# o_clone_rev_e_buttons.net
KiCad netlist of a schematic drawn in EAGLE
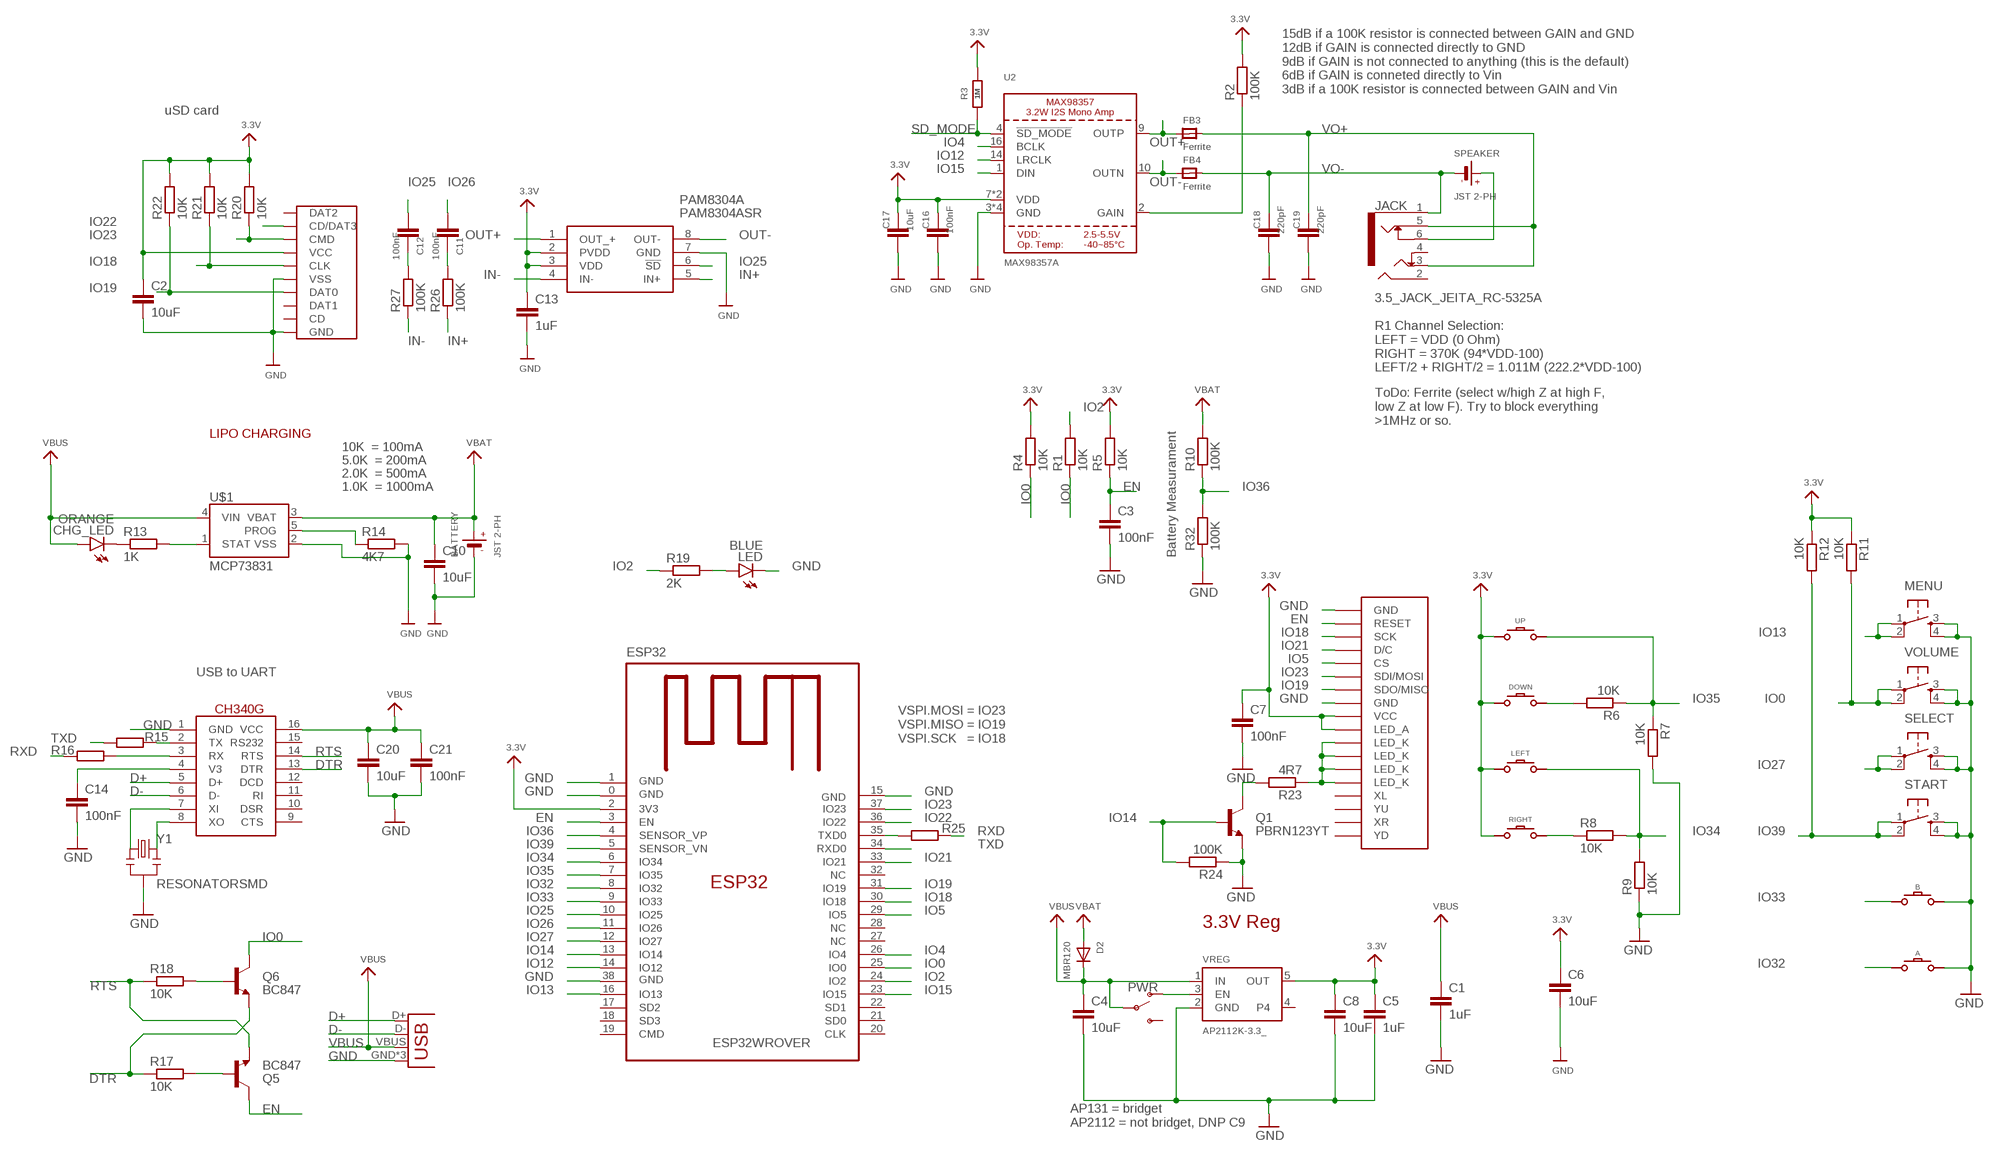
[diagram p0: schematic, sheet 1]

(export (version "E")
  (design (tool "Eeschema 10.0.6"))
  (components
    (comp (ref "A")
      (value "CONDUCTIVE_BUTTONCONDUCTIVE_BUTTON_THICK")
      (footprint "eagle-import:CONDUCTIVE_BUTTON_THICK")
      (libsource (lib "eagle-import") (part "CONDUCTIVE_BUTTONCONDUCTIVE_BUTTON_THICK"))
    )
    (comp (ref "B")
      (value "CONDUCTIVE_BUTTONCONDUCTIVE_BUTTON_THICK")
      (footprint "eagle-import:CONDUCTIVE_BUTTON_THICK")
      (libsource (lib "eagle-import") (part "CONDUCTIVE_BUTTONCONDUCTIVE_BUTTON_THICK"))
    )
    (comp (ref "BATTERY")
      (value "JST 2-PH")
      (footprint "eagle-import:JSTPH2")
      (libsource (lib "eagle-import") (part "JST_CONNECTOR"))
    )
    (comp (ref "C1")
      (value "1uF")
      (footprint "eagle-import:C0805K")
      (libsource (lib "eagle-import") (part "C-EUC0805K"))
    )
    (comp (ref "C2")
      (value "10uF")
      (footprint "eagle-import:C0805K")
      (libsource (lib "eagle-import") (part "C-EUC0805K"))
    )
    (comp (ref "C3")
      (value "100nF")
      (footprint "eagle-import:C0805K")
      (libsource (lib "eagle-import") (part "C-EUC0805K"))
    )
    (comp (ref "C4")
      (value "10uF")
      (footprint "eagle-import:C0805K")
      (libsource (lib "eagle-import") (part "C-EUC0805K"))
    )
    (comp (ref "C5")
      (value "1uF")
      (footprint "eagle-import:C0805K")
      (libsource (lib "eagle-import") (part "C-EUC0805K"))
    )
    (comp (ref "C6")
      (value "10uF")
      (footprint "eagle-import:C0805K")
      (libsource (lib "eagle-import") (part "C-EUC0805K"))
    )
    (comp (ref "C7")
      (value "100nF")
      (footprint "eagle-import:C0805")
      (libsource (lib "eagle-import") (part "C-EUC0805"))
    )
    (comp (ref "C8")
      (value "10uF")
      (footprint "eagle-import:C0805K")
      (libsource (lib "eagle-import") (part "C-EUC0805K"))
    )
    (comp (ref "C10")
      (value "10uF")
      (footprint "eagle-import:C0805K")
      (libsource (lib "eagle-import") (part "C-EUC0805K"))
    )
    (comp (ref "C11")
      (value "100nF")
      (footprint "eagle-import:C0805K")
      (libsource (lib "eagle-import") (part "C-EUC0805K"))
    )
    (comp (ref "C12")
      (value "100nF")
      (footprint "eagle-import:C0805K")
      (libsource (lib "eagle-import") (part "C-EUC0805K"))
    )
    (comp (ref "C13")
      (value "1uF")
      (footprint "eagle-import:C0805K")
      (libsource (lib "eagle-import") (part "C-EUC0805K"))
    )
    (comp (ref "C14")
      (value "100nF")
      (footprint "eagle-import:C0805K")
      (libsource (lib "eagle-import") (part "C-EUC0805K"))
    )
    (comp (ref "C16")
      (value "100nF")
      (footprint "eagle-import:C0805K")
      (libsource (lib "eagle-import") (part "C-EUC0805K"))
    )
    (comp (ref "C17")
      (value "10uF")
      (footprint "eagle-import:C0805K")
      (libsource (lib "eagle-import") (part "C-EUC0805K"))
    )
    (comp (ref "C18")
      (value "220pF")
      (footprint "eagle-import:C0805K")
      (libsource (lib "eagle-import") (part "C-EUC0805K"))
    )
    (comp (ref "C19")
      (value "220pF")
      (footprint "eagle-import:C0805K")
      (libsource (lib "eagle-import") (part "C-EUC0805K"))
    )
    (comp (ref "C20")
      (value "10uF")
      (footprint "eagle-import:C0805K")
      (libsource (lib "eagle-import") (part "C-EUC0805K"))
    )
    (comp (ref "C21")
      (value "100nF")
      (footprint "eagle-import:C0805K")
      (libsource (lib "eagle-import") (part "C-EUC0805K"))
    )
    (comp (ref "CHG_LED")
      (value "ORANGE")
      (footprint "eagle-import:CHIPLED_0805")
      (libsource (lib "eagle-import") (part "LEDCHIPLED_0805"))
    )
    (comp (ref "D2")
      (value "MBR120")
      (footprint "eagle-import:SOD-123")
      (libsource (lib "eagle-import") (part "DIODESOD-123"))
    )
    (comp (ref "DOWN")
      (value "CONDUCTIVE_BUTTONCONDUCTIVE_BUTTON_DIRECTIONAL_THICK")
      (footprint "eagle-import:CONDUCTIVE_BUTTON_DIRECTIONAL_THICK")
      (libsource (lib "eagle-import") (part "CONDUCTIVE_BUTTONCONDUCTIVE_BUTTON_DIRECTIONAL_THICK"))
    )
    (comp (ref "ESP32")
      (value "ESP32WROVER")
      (footprint "eagle-import:ESP32WROVER")
      (libsource (lib "eagle-import") (part "ESP32WROVER"))
    )
    (comp (ref "FB3")
      (value "Ferrite")
      (footprint "eagle-import:0805")
      (libsource (lib "eagle-import") (part "FERRITE0805"))
    )
    (comp (ref "FB4")
      (value "Ferrite")
      (footprint "eagle-import:0805")
      (libsource (lib "eagle-import") (part "FERRITE0805"))
    )
    (comp (ref "JACK")
      (value "3.5_JACK_JEITA_RC-5325A")
      (footprint "eagle-import:3.5_JACK_JEITA_RC-5325A")
      (libsource (lib "eagle-import") (part "3.5_JACK_JEITA_RC-5325A"))
    )
    (comp (ref "LCD")
      (value "ILI9341_3.2LCD_")
      (footprint "eagle-import:LI9341_3.2LCD")
      (libsource (lib "eagle-import") (part "ILI9341_3.2LCD_"))
    )
    (comp (ref "LED")
      (value "BLUE")
      (footprint "eagle-import:CHIPLED_0805")
      (libsource (lib "eagle-import") (part "LEDCHIPLED_0805"))
    )
    (comp (ref "LEFT")
      (value "CONDUCTIVE_BUTTONCONDUCTIVE_BUTTON_DIRECTIONAL_THICK")
      (footprint "eagle-import:CONDUCTIVE_BUTTON_DIRECTIONAL_THICK")
      (libsource (lib "eagle-import") (part "CONDUCTIVE_BUTTONCONDUCTIVE_BUTTON_DIRECTIONAL_THICK"))
    )
    (comp (ref "MENU")
      (value "TACTILE_SWITCHE_5X5_MICRO\"")
      (footprint "eagle-import:TACTILE_SWITCH_5X5_MICRO")
      (libsource (lib "eagle-import") (part "TACTILE_SWITCHE_5X5_MICRO{dblquote}"))
    )
    (comp (ref "PAM8304A")
      (value "PAM8304ASR")
      (footprint "eagle-import:SOP65P490X110-8N")
      (fields (field (name "MOUSER_PART_NUMBER") "621-PAM8304ASR"))
      (libsource (lib "eagle-import") (part "PAM8304ASR"))
    )
    (comp (ref "PWR")
      (value "SWITCH-SPDT-SMD-RIGHT-ANGLE")
      (footprint "eagle-import:SWITCH_SPST_SMD_A")
      (libsource (lib "eagle-import") (part "SWITCH-SPDT-SMD-RIGHT-ANGLE"))
    )
    (comp (ref "Q1")
      (value "PBRN123YT")
      (footprint "eagle-import:SOT23-3")
      (libsource (lib "eagle-import") (part "TRANSISTOR_NPNSOT23-3"))
    )
    (comp (ref "Q5")
      (value "BC847")
      (footprint "eagle-import:SOT23-3")
      (libsource (lib "eagle-import") (part "TRANSISTOR_NPNSOT23-3"))
    )
    (comp (ref "Q6")
      (value "BC847")
      (footprint "eagle-import:SOT23-3")
      (libsource (lib "eagle-import") (part "TRANSISTOR_NPNSOT23-3"))
    )
    (comp (ref "R1")
      (value "10K")
      (footprint "eagle-import:R0805")
      (libsource (lib "eagle-import") (part "R-EU_R0805"))
    )
    (comp (ref "R2")
      (value "100K")
      (footprint "eagle-import:R0805")
      (libsource (lib "eagle-import") (part "R-EU_R0805"))
    )
    (comp (ref "R3")
      (value "1M")
      (footprint "eagle-import:R0805")
      (libsource (lib "eagle-import") (part "R-EU_R0805"))
    )
    (comp (ref "R4")
      (value "10K")
      (footprint "eagle-import:R0805")
      (libsource (lib "eagle-import") (part "R-EU_R0805"))
    )
    (comp (ref "R5")
      (value "10K")
      (footprint "eagle-import:R0805")
      (libsource (lib "eagle-import") (part "R-EU_R0805"))
    )
    (comp (ref "R6")
      (value "10K")
      (footprint "eagle-import:R0805")
      (libsource (lib "eagle-import") (part "R-EU_R0805"))
    )
    (comp (ref "R7")
      (value "10K")
      (footprint "eagle-import:R0805")
      (libsource (lib "eagle-import") (part "R-EU_R0805"))
    )
    (comp (ref "R8")
      (value "10K")
      (footprint "eagle-import:R0805")
      (libsource (lib "eagle-import") (part "R-EU_R0805"))
    )
    (comp (ref "R9")
      (value "10K")
      (footprint "eagle-import:R0805")
      (libsource (lib "eagle-import") (part "R-EU_R0805"))
    )
    (comp (ref "R10")
      (value "100K")
      (footprint "eagle-import:R0805")
      (libsource (lib "eagle-import") (part "R-EU_R0805"))
    )
    (comp (ref "R11")
      (value "10K")
      (footprint "eagle-import:R0805")
      (libsource (lib "eagle-import") (part "R-EU_R0805"))
    )
    (comp (ref "R12")
      (value "10K")
      (footprint "eagle-import:R0805")
      (libsource (lib "eagle-import") (part "R-EU_R0805"))
    )
    (comp (ref "R13")
      (value "1K")
      (footprint "eagle-import:R0805")
      (libsource (lib "eagle-import") (part "R-EU_R0805"))
    )
    (comp (ref "R14")
      (value "4K7")
      (footprint "eagle-import:R0805")
      (libsource (lib "eagle-import") (part "R-EU_R0805"))
    )
    (comp (ref "R15")
      (value "470R")
      (footprint "eagle-import:R0805")
      (libsource (lib "eagle-import") (part "R-EU_R0805"))
    )
    (comp (ref "R16")
      (value "470R")
      (footprint "eagle-import:R0805")
      (libsource (lib "eagle-import") (part "R-EU_R0805"))
    )
    (comp (ref "R17")
      (value "10K")
      (footprint "eagle-import:R0805")
      (libsource (lib "eagle-import") (part "R-EU_R0805"))
    )
    (comp (ref "R18")
      (value "10K")
      (footprint "eagle-import:R0805")
      (libsource (lib "eagle-import") (part "R-EU_R0805"))
    )
    (comp (ref "R19")
      (value "2K")
      (footprint "eagle-import:R0805")
      (libsource (lib "eagle-import") (part "R-EU_R0805"))
    )
    (comp (ref "R20")
      (value "10K")
      (footprint "eagle-import:R0805")
      (libsource (lib "eagle-import") (part "R-EU_R0805"))
    )
    (comp (ref "R21")
      (value "10K")
      (footprint "eagle-import:R0805")
      (libsource (lib "eagle-import") (part "R-EU_R0805"))
    )
    (comp (ref "R22")
      (value "10K")
      (footprint "eagle-import:R0805")
      (libsource (lib "eagle-import") (part "R-EU_R0805"))
    )
    (comp (ref "R23")
      (value "4R7")
      (footprint "eagle-import:R0805")
      (libsource (lib "eagle-import") (part "R-EU_R0805"))
    )
    (comp (ref "R24")
      (value "100K")
      (footprint "eagle-import:R0805")
      (libsource (lib "eagle-import") (part "R-EU_R0805"))
    )
    (comp (ref "R25")
      (value "470R")
      (footprint "eagle-import:R0805")
      (libsource (lib "eagle-import") (part "R-EU_R0805"))
    )
    (comp (ref "R26")
      (value "100K")
      (footprint "eagle-import:R0805")
      (libsource (lib "eagle-import") (part "R-EU_R0805"))
    )
    (comp (ref "R27")
      (value "100K")
      (footprint "eagle-import:R0805")
      (libsource (lib "eagle-import") (part "R-EU_R0805"))
    )
    (comp (ref "R32")
      (value "100K")
      (footprint "eagle-import:R0805")
      (libsource (lib "eagle-import") (part "R-EU_R0805"))
    )
    (comp (ref "RIGHT")
      (value "CONDUCTIVE_BUTTONCONDUCTIVE_BUTTON_DIRECTIONAL_THICK")
      (footprint "eagle-import:CONDUCTIVE_BUTTON_DIRECTIONAL_THICK")
      (libsource (lib "eagle-import") (part "CONDUCTIVE_BUTTONCONDUCTIVE_BUTTON_DIRECTIONAL_THICK"))
    )
    (comp (ref "SD_CARD")
      (value "MICRO_SD_CARD\"")
      (footprint "eagle-import:TFP09-2--12B")
      (libsource (lib "eagle-import") (part "MICRO_SD_CARD{dblquote}"))
    )
    (comp (ref "SELECT")
      (value "TACTILE_SWITCHE_5X5_MICRO\"")
      (footprint "eagle-import:TACTILE_SWITCH_5X5_MICRO")
      (libsource (lib "eagle-import") (part "TACTILE_SWITCHE_5X5_MICRO{dblquote}"))
    )
    (comp (ref "SPEAKER")
      (value "JST 2-PH")
      (footprint "eagle-import:JSTPH2")
      (libsource (lib "eagle-import") (part "JST_CONNECTOR"))
    )
    (comp (ref "START")
      (value "TACTILE_SWITCHE_5X5_MICRO\"")
      (footprint "eagle-import:TACTILE_SWITCH_5X5_MICRO")
      (libsource (lib "eagle-import") (part "TACTILE_SWITCHE_5X5_MICRO{dblquote}"))
    )
    (comp (ref "U$1")
      (value "MCP73831")
      (footprint "eagle-import:SOT95P290X120-5")
      (libsource (lib "eagle-import") (part "MCP73831"))
    )
    (comp (ref "U$23")
      (value "CH340G")
      (footprint "eagle-import:SO16")
      (libsource (lib "eagle-import") (part "CH340G"))
    )
    (comp (ref "U2")
      (value "MAX98357A")
      (footprint "eagle-import:QFN16_3MM")
      (libsource (lib "eagle-import") (part "AUDIOAMP_MAX98357"))
    )
    (comp (ref "UP")
      (value "CONDUCTIVE_BUTTONCONDUCTIVE_BUTTON_DIRECTIONAL_THICK")
      (footprint "eagle-import:CONDUCTIVE_BUTTON_DIRECTIONAL_THICK")
      (libsource (lib "eagle-import") (part "CONDUCTIVE_BUTTONCONDUCTIVE_BUTTON_DIRECTIONAL_THICK"))
    )
    (comp (ref "USB")
      (value "USB_MICRO_ATTEND_")
      (footprint "eagle-import:USB_MICRO")
      (libsource (lib "eagle-import") (part "USB_MICRO_ATTEND_"))
    )
    (comp (ref "VOLUME")
      (value "TACTILE_SWITCHE_5X5_MICRO\"")
      (footprint "eagle-import:TACTILE_SWITCH_5X5_MICRO")
      (libsource (lib "eagle-import") (part "TACTILE_SWITCHE_5X5_MICRO{dblquote}"))
    )
    (comp (ref "VREG")
      (value "AP2112K-3.3_")
      (footprint "eagle-import:SOT95P290X120-5")
      (libsource (lib "eagle-import") (part "AP2112K-3.3_"))
    )
    (comp (ref "Y1")
      (value "RESONATORSMD")
      (footprint "eagle-import:RESONATOR-SMD")
      (libsource (lib "eagle-import") (part "RESONATORSMD"))
    )
  )
  (nets
    (net (code "1") (name "/D+") (class "Default")
      (node (ref "U$23") (pin "5") (pinfunction "D+_5") (pintype "bidirectional"))
      (node (ref "USB") (pin "D+") (pinfunction "D+_D+") (pintype "bidirectional"))
    )
    (net (code "2") (name "/D-") (class "Default")
      (node (ref "U$23") (pin "6") (pinfunction "D-_6") (pintype "bidirectional"))
      (node (ref "USB") (pin "D-") (pinfunction "D-_D-") (pintype "bidirectional"))
    )
    (net (code "3") (name "/DTR") (class "Default")
      (node (ref "Q6") (pin "2") (pinfunction "E_2") (pintype "passive"))
      (node (ref "R17") (pin "1") (pinfunction "1_1") (pintype "passive"))
      (node (ref "U$23") (pin "13") (pinfunction "DTR_13") (pintype "bidirectional"))
    )
    (net (code "4") (name "/EN") (class "Default")
      (node (ref "C3") (pin "1") (pinfunction "1_1") (pintype "passive"))
      (node (ref "ESP32") (pin "3") (pinfunction "EN_3") (pintype "bidirectional"))
      (node (ref "LCD") (pin "P$2") (pinfunction "RESET_P$2") (pintype "bidirectional"))
      (node (ref "Q5") (pin "3") (pinfunction "C_3") (pintype "passive"))
      (node (ref "R5") (pin "1") (pinfunction "1_1") (pintype "passive"))
    )
    (net (code "5") (name "/IN+") (class "Default")
      (node (ref "PAM8304A") (pin "5") (pinfunction "IN+_5") (pintype "bidirectional"))
      (node (ref "R26") (pin "1") (pinfunction "1_1") (pintype "passive"))
    )
    (net (code "6") (name "/IN-") (class "Default")
      (node (ref "PAM8304A") (pin "4") (pinfunction "IN-_4") (pintype "bidirectional"))
      (node (ref "R27") (pin "1") (pinfunction "1_1") (pintype "passive"))
    )
    (net (code "7") (name "/IO0") (class "Default")
      (node (ref "ESP32") (pin "25") (pinfunction "IO0_25") (pintype "bidirectional"))
      (node (ref "Q6") (pin "3") (pinfunction "C_3") (pintype "passive"))
      (node (ref "R1") (pin "1") (pinfunction "1_1") (pintype "passive"))
      (node (ref "R11") (pin "2") (pinfunction "2_2") (pintype "passive"))
      (node (ref "R4") (pin "1") (pinfunction "1_1") (pintype "passive"))
      (node (ref "VOLUME") (pin "1") (pinfunction "1_1") (pintype "passive"))
      (node (ref "VOLUME") (pin "2") (pinfunction "2_2") (pintype "passive"))
    )
    (net (code "8") (name "/IO2") (class "Default")
      (node (ref "ESP32") (pin "24") (pinfunction "IO2_24") (pintype "bidirectional"))
      (node (ref "R1") (pin "2") (pinfunction "2_2") (pintype "passive"))
      (node (ref "R19") (pin "1") (pinfunction "1_1") (pintype "passive"))
    )
    (net (code "9") (name "/IO4") (class "Default")
      (node (ref "ESP32") (pin "26") (pinfunction "IO4_26") (pintype "bidirectional"))
      (node (ref "U2") (pin "16") (pinfunction "BCLK_16") (pintype "bidirectional"))
    )
    (net (code "10") (name "/IO5") (class "Default")
      (node (ref "ESP32") (pin "29") (pinfunction "IO5_29") (pintype "bidirectional"))
      (node (ref "LCD") (pin "P$5") (pinfunction "CS_P$5") (pintype "bidirectional"))
    )
    (net (code "11") (name "/IO12") (class "Default")
      (node (ref "ESP32") (pin "14") (pinfunction "IO12_14") (pintype "bidirectional"))
      (node (ref "U2") (pin "14") (pinfunction "LRCLK_14") (pintype "bidirectional"))
    )
    (net (code "12") (name "/IO13") (class "Default")
      (node (ref "ESP32") (pin "16") (pinfunction "IO13_16") (pintype "bidirectional"))
      (node (ref "MENU") (pin "1") (pinfunction "1_1") (pintype "passive"))
      (node (ref "MENU") (pin "2") (pinfunction "2_2") (pintype "passive"))
    )
    (net (code "13") (name "/IO14") (class "Default")
      (node (ref "ESP32") (pin "13") (pinfunction "IO14_13") (pintype "bidirectional"))
      (node (ref "Q1") (pin "1") (pinfunction "B_1") (pintype "passive"))
      (node (ref "R24") (pin "2") (pinfunction "2_2") (pintype "passive"))
    )
    (net (code "14") (name "/IO15") (class "Default")
      (node (ref "ESP32") (pin "23") (pinfunction "IO15_23") (pintype "bidirectional"))
      (node (ref "U2") (pin "1") (pinfunction "DIN_1") (pintype "bidirectional"))
    )
    (net (code "15") (name "/IO18") (class "Default")
      (node (ref "ESP32") (pin "30") (pinfunction "IO18_30") (pintype "bidirectional"))
      (node (ref "LCD") (pin "P$3") (pinfunction "SCK_P$3") (pintype "bidirectional"))
      (node (ref "R21") (pin "1") (pinfunction "1_1") (pintype "passive"))
      (node (ref "SD_CARD") (pin "CLK") (pinfunction "CLK_CLK") (pintype "bidirectional"))
    )
    (net (code "16") (name "/IO19") (class "Default")
      (node (ref "ESP32") (pin "31") (pinfunction "IO19_31") (pintype "bidirectional"))
      (node (ref "LCD") (pin "P$7") (pinfunction "SDO/MISO_P$7") (pintype "bidirectional"))
      (node (ref "R22") (pin "1") (pinfunction "1_1") (pintype "passive"))
      (node (ref "SD_CARD") (pin "DAT0") (pinfunction "DAT0_DAT0") (pintype "bidirectional"))
    )
    (net (code "17") (name "/IO21") (class "Default")
      (node (ref "ESP32") (pin "33") (pinfunction "IO21_33") (pintype "bidirectional"))
      (node (ref "LCD") (pin "P$4") (pinfunction "D/C_P$4") (pintype "bidirectional"))
    )
    (net (code "18") (name "/IO22") (class "Default")
      (node (ref "ESP32") (pin "36") (pinfunction "IO22_36") (pintype "bidirectional"))
      (node (ref "SD_CARD") (pin "CD/DAT3") (pinfunction "CD/DAT3_CD/DAT3") (pintype "bidirectional"))
    )
    (net (code "19") (name "/IO23") (class "Default")
      (node (ref "ESP32") (pin "37") (pinfunction "IO23_37") (pintype "bidirectional"))
      (node (ref "LCD") (pin "P$6") (pinfunction "SDI/MOSI_P$6") (pintype "bidirectional"))
      (node (ref "R20") (pin "1") (pinfunction "1_1") (pintype "passive"))
      (node (ref "SD_CARD") (pin "CMD") (pinfunction "CMD_CMD") (pintype "bidirectional"))
    )
    (net (code "20") (name "/IO25") (class "Default")
      (node (ref "C12") (pin "2") (pinfunction "2_2") (pintype "passive"))
      (node (ref "ESP32") (pin "10") (pinfunction "IO25_10") (pintype "bidirectional"))
      (node (ref "PAM8304A") (pin "6") (pinfunction "~{SD}_6") (pintype "bidirectional"))
    )
    (net (code "21") (name "/IO26") (class "Default")
      (node (ref "C11") (pin "2") (pinfunction "2_2") (pintype "passive"))
      (node (ref "ESP32") (pin "11") (pinfunction "IO26_11") (pintype "bidirectional"))
    )
    (net (code "22") (name "/IO27") (class "Default")
      (node (ref "ESP32") (pin "12") (pinfunction "IO27_12") (pintype "bidirectional"))
      (node (ref "SELECT") (pin "1") (pinfunction "1_1") (pintype "passive"))
      (node (ref "SELECT") (pin "2") (pinfunction "2_2") (pintype "passive"))
    )
    (net (code "23") (name "/IO32") (class "Default")
      (node (ref "A") (pin "P$GND") (pinfunction "P$GND_P$GND") (pintype "bidirectional"))
      (node (ref "ESP32") (pin "8") (pinfunction "IO32_8") (pintype "bidirectional"))
    )
    (net (code "24") (name "/IO33") (class "Default")
      (node (ref "B") (pin "P$GND") (pinfunction "P$GND_P$GND") (pintype "bidirectional"))
      (node (ref "ESP32") (pin "9") (pinfunction "IO33_9") (pintype "bidirectional"))
    )
    (net (code "25") (name "/IO34") (class "Default")
      (node (ref "ESP32") (pin "6") (pinfunction "IO34_6") (pintype "bidirectional"))
      (node (ref "LEFT") (pin "P$ACTIVE") (pinfunction "P$ACTIVE_P$ACTIVE") (pintype "bidirectional"))
      (node (ref "R8") (pin "2") (pinfunction "2_2") (pintype "passive"))
      (node (ref "R9") (pin "2") (pinfunction "2_2") (pintype "passive"))
    )
    (net (code "26") (name "/IO35") (class "Default")
      (node (ref "ESP32") (pin "7") (pinfunction "IO35_7") (pintype "bidirectional"))
      (node (ref "R6") (pin "1") (pinfunction "1_1") (pintype "passive"))
      (node (ref "R7") (pin "1") (pinfunction "1_1") (pintype "passive"))
      (node (ref "UP") (pin "P$ACTIVE") (pinfunction "P$ACTIVE_P$ACTIVE") (pintype "bidirectional"))
    )
    (net (code "27") (name "/IO36") (class "Default")
      (node (ref "ESP32") (pin "4") (pinfunction "SENSOR_VP_4") (pintype "bidirectional"))
      (node (ref "R10") (pin "1") (pinfunction "1_1") (pintype "passive"))
      (node (ref "R32") (pin "2") (pinfunction "2_2") (pintype "passive"))
    )
    (net (code "28") (name "/IO39") (class "Default")
      (node (ref "ESP32") (pin "5") (pinfunction "SENSOR_VN_5") (pintype "bidirectional"))
      (node (ref "R12") (pin "2") (pinfunction "2_2") (pintype "passive"))
      (node (ref "START") (pin "1") (pinfunction "1_1") (pintype "passive"))
      (node (ref "START") (pin "2") (pinfunction "2_2") (pintype "passive"))
    )
    (net (code "29") (name "/OUT+") (class "Default")
      (node (ref "FB3") (pin "1") (pinfunction "P$1_1") (pintype "passive"))
      (node (ref "PAM8304A") (pin "1") (pinfunction "OUT_+_1") (pintype "bidirectional"))
      (node (ref "U2") (pin "9") (pinfunction "OUTP_9") (pintype "output"))
    )
    (net (code "30") (name "/OUT-") (class "Default")
      (node (ref "FB4") (pin "1") (pinfunction "P$1_1") (pintype "passive"))
      (node (ref "PAM8304A") (pin "8") (pinfunction "OUT-_8") (pintype "bidirectional"))
      (node (ref "U2") (pin "10") (pinfunction "OUTN_10") (pintype "output"))
    )
    (net (code "31") (name "/RTS") (class "Default")
      (node (ref "Q5") (pin "2") (pinfunction "E_2") (pintype "passive"))
      (node (ref "R18") (pin "1") (pinfunction "1_1") (pintype "passive"))
      (node (ref "U$23") (pin "14") (pinfunction "RTS_14") (pintype "bidirectional"))
    )
    (net (code "32") (name "/RXD") (class "Default")
      (node (ref "R16") (pin "2") (pinfunction "2_2") (pintype "passive"))
      (node (ref "R25") (pin "1") (pinfunction "1_1") (pintype "passive"))
    )
    (net (code "33") (name "/SD_MODE") (class "Default")
      (node (ref "R3") (pin "1") (pinfunction "1_1") (pintype "passive"))
      (node (ref "U2") (pin "4") (pinfunction "~{SD_MODE}_4") (pintype "bidirectional"))
    )
    (net (code "34") (name "/TXD") (class "Default")
      (node (ref "ESP32") (pin "34") (pinfunction "RXD0_34") (pintype "bidirectional"))
      (node (ref "R15") (pin "2") (pinfunction "2_2") (pintype "passive"))
    )
    (net (code "35") (name "/VO+") (class "Default")
      (node (ref "C19") (pin "1") (pinfunction "1_1") (pintype "passive"))
      (node (ref "FB3") (pin "2") (pinfunction "P$2_2") (pintype "passive"))
      (node (ref "JACK") (pin "3") (pinfunction "3_3") (pintype "bidirectional"))
      (node (ref "JACK") (pin "5") (pinfunction "5_5") (pintype "bidirectional"))
    )
    (net (code "36") (name "/VO-") (class "Default")
      (node (ref "C18") (pin "1") (pinfunction "1_1") (pintype "passive"))
      (node (ref "FB4") (pin "2") (pinfunction "P$2_2") (pintype "passive"))
      (node (ref "JACK") (pin "1") (pinfunction "1_1") (pintype "bidirectional"))
      (node (ref "SPEAKER") (pin "1") (pinfunction "-_1") (pintype "passive"))
    )
    (net (code "37") (name "3.3V") (class "Default")
      (node (ref "C13") (pin "1") (pinfunction "1_1") (pintype "passive"))
      (node (ref "C16") (pin "1") (pinfunction "1_1") (pintype "passive"))
      (node (ref "C17") (pin "1") (pinfunction "1_1") (pintype "passive"))
      (node (ref "C2") (pin "1") (pinfunction "1_1") (pintype "passive"))
      (node (ref "C5") (pin "1") (pinfunction "1_1") (pintype "passive"))
      (node (ref "C6") (pin "1") (pinfunction "1_1") (pintype "passive"))
      (node (ref "C7") (pin "1") (pinfunction "1_1") (pintype "passive"))
      (node (ref "C8") (pin "1") (pinfunction "1_1") (pintype "passive"))
      (node (ref "DOWN") (pin "P$GND") (pinfunction "P$GND_P$GND") (pintype "bidirectional"))
      (node (ref "ESP32") (pin "2") (pinfunction "3V3_2") (pintype "power_in"))
      (node (ref "LCD") (pin "P$10") (pinfunction "LED_A_P$10") (pintype "bidirectional"))
      (node (ref "LCD") (pin "P$9") (pinfunction "VCC_P$9") (pintype "bidirectional"))
      (node (ref "LEFT") (pin "P$GND") (pinfunction "P$GND_P$GND") (pintype "bidirectional"))
      (node (ref "PAM8304A") (pin "2") (pinfunction "PVDD_2") (pintype "bidirectional"))
      (node (ref "PAM8304A") (pin "3") (pinfunction "VDD_3") (pintype "bidirectional"))
      (node (ref "R11") (pin "1") (pinfunction "1_1") (pintype "passive"))
      (node (ref "R12") (pin "1") (pinfunction "1_1") (pintype "passive"))
      (node (ref "R2") (pin "2") (pinfunction "2_2") (pintype "passive"))
      (node (ref "R20") (pin "2") (pinfunction "2_2") (pintype "passive"))
      (node (ref "R21") (pin "2") (pinfunction "2_2") (pintype "passive"))
      (node (ref "R22") (pin "2") (pinfunction "2_2") (pintype "passive"))
      (node (ref "R3") (pin "2") (pinfunction "2_2") (pintype "passive"))
      (node (ref "R4") (pin "2") (pinfunction "2_2") (pintype "passive"))
      (node (ref "R5") (pin "2") (pinfunction "2_2") (pintype "passive"))
      (node (ref "RIGHT") (pin "P$GND") (pinfunction "P$GND_P$GND") (pintype "bidirectional"))
      (node (ref "SD_CARD") (pin "VCC") (pinfunction "VCC_VCC") (pintype "bidirectional"))
      (node (ref "U2") (pin "7") (pinfunction "VDD_7") (pintype "power_in"))
      (node (ref "U2") (pin "8") (pinfunction "VDD_8") (pintype "power_in"))
      (node (ref "UP") (pin "P$GND") (pinfunction "P$GND_P$GND") (pintype "bidirectional"))
      (node (ref "VREG") (pin "5") (pinfunction "OUT_5") (pintype "bidirectional"))
    )
    (net (code "38") (name "GND") (class "Default")
      (node (ref "A") (pin "P$ACTIVE") (pinfunction "P$ACTIVE_P$ACTIVE") (pintype "bidirectional"))
      (node (ref "B") (pin "P$ACTIVE") (pinfunction "P$ACTIVE_P$ACTIVE") (pintype "bidirectional"))
      (node (ref "BATTERY") (pin "1") (pinfunction "-_1") (pintype "passive"))
      (node (ref "C1") (pin "2") (pinfunction "2_2") (pintype "passive"))
      (node (ref "C10") (pin "2") (pinfunction "2_2") (pintype "passive"))
      (node (ref "C13") (pin "2") (pinfunction "2_2") (pintype "passive"))
      (node (ref "C14") (pin "2") (pinfunction "2_2") (pintype "passive"))
      (node (ref "C16") (pin "2") (pinfunction "2_2") (pintype "passive"))
      (node (ref "C17") (pin "2") (pinfunction "2_2") (pintype "passive"))
      (node (ref "C18") (pin "2") (pinfunction "2_2") (pintype "passive"))
      (node (ref "C19") (pin "2") (pinfunction "2_2") (pintype "passive"))
      (node (ref "C2") (pin "2") (pinfunction "2_2") (pintype "passive"))
      (node (ref "C20") (pin "2") (pinfunction "2_2") (pintype "passive"))
      (node (ref "C21") (pin "2") (pinfunction "2_2") (pintype "passive"))
      (node (ref "C3") (pin "2") (pinfunction "2_2") (pintype "passive"))
      (node (ref "C4") (pin "2") (pinfunction "2_2") (pintype "passive"))
      (node (ref "C5") (pin "2") (pinfunction "2_2") (pintype "passive"))
      (node (ref "C6") (pin "2") (pinfunction "2_2") (pintype "passive"))
      (node (ref "C7") (pin "2") (pinfunction "2_2") (pintype "passive"))
      (node (ref "C8") (pin "2") (pinfunction "2_2") (pintype "passive"))
      (node (ref "ESP32") (pin "0") (pinfunction "GND_0") (pintype "power_in"))
      (node (ref "ESP32") (pin "1") (pinfunction "GND_1") (pintype "power_in"))
      (node (ref "ESP32") (pin "15") (pinfunction "GND_15") (pintype "power_in"))
      (node (ref "ESP32") (pin "38") (pinfunction "GND_38") (pintype "power_in"))
      (node (ref "LCD") (pin "P$1") (pinfunction "GND_P$1") (pintype "bidirectional"))
      (node (ref "LCD") (pin "P$8") (pinfunction "GND_P$8") (pintype "bidirectional"))
      (node (ref "LED") (pin "C") (pinfunction "C_C") (pintype "passive"))
      (node (ref "MENU") (pin "3") (pinfunction "3_3") (pintype "passive"))
      (node (ref "MENU") (pin "4") (pinfunction "4_4") (pintype "passive"))
      (node (ref "PAM8304A") (pin "7") (pinfunction "GND_7") (pintype "bidirectional"))
      (node (ref "Q1") (pin "2") (pinfunction "E_2") (pintype "passive"))
      (node (ref "R14") (pin "2") (pinfunction "2_2") (pintype "passive"))
      (node (ref "R24") (pin "1") (pinfunction "1_1") (pintype "passive"))
      (node (ref "R32") (pin "1") (pinfunction "1_1") (pintype "passive"))
      (node (ref "R7") (pin "2") (pinfunction "2_2") (pintype "passive"))
      (node (ref "R9") (pin "1") (pinfunction "1_1") (pintype "passive"))
      (node (ref "SD_CARD") (pin "GND") (pinfunction "GND_GND") (pintype "bidirectional"))
      (node (ref "SD_CARD") (pin "GND@1") (pinfunction "GND_GND@1") (pintype "bidirectional"))
      (node (ref "SD_CARD") (pin "GND@2") (pinfunction "GND_GND@2") (pintype "bidirectional"))
      (node (ref "SD_CARD") (pin "GND@3") (pinfunction "VSS_GND@3") (pintype "bidirectional"))
      (node (ref "SD_CARD") (pin "VSS") (pinfunction "GND_VSS") (pintype "bidirectional"))
      (node (ref "SELECT") (pin "3") (pinfunction "3_3") (pintype "passive"))
      (node (ref "SELECT") (pin "4") (pinfunction "4_4") (pintype "passive"))
      (node (ref "START") (pin "3") (pinfunction "3_3") (pintype "passive"))
      (node (ref "START") (pin "4") (pinfunction "4_4") (pintype "passive"))
      (node (ref "U$1") (pin "2") (pinfunction "VSS_2") (pintype "power_in"))
      (node (ref "U$23") (pin "1") (pinfunction "GND_1") (pintype "bidirectional"))
      (node (ref "U2") (pin "11") (pinfunction "GND_11") (pintype "power_in"))
      (node (ref "U2") (pin "15") (pinfunction "GND_15") (pintype "power_in"))
      (node (ref "U2") (pin "3") (pinfunction "GND_3") (pintype "power_in"))
      (node (ref "U2") (pin "THERMAL") (pinfunction "GND_THERMAL") (pintype "power_in"))
      (node (ref "USB") (pin "GND") (pinfunction "GND_GND") (pintype "bidirectional"))
      (node (ref "USB") (pin "GND@2") (pinfunction "GND_GND@2") (pintype "bidirectional"))
      (node (ref "USB") (pin "GND@3") (pinfunction "GND_GND@3") (pintype "bidirectional"))
      (node (ref "VOLUME") (pin "3") (pinfunction "3_3") (pintype "passive"))
      (node (ref "VOLUME") (pin "4") (pinfunction "4_4") (pintype "passive"))
      (node (ref "VREG") (pin "2") (pinfunction "GND_2") (pintype "bidirectional"))
      (node (ref "Y1") (pin "2") (pinfunction "2_2") (pintype "passive"))
    )
    (net (code "39") (name "Net-(C11-Pad1)") (class "Default")
      (node (ref "C11") (pin "1") (pinfunction "1_1") (pintype "passive"))
      (node (ref "R26") (pin "2") (pinfunction "2_2") (pintype "passive"))
    )
    (net (code "40") (name "Net-(C12-Pad1)") (class "Default")
      (node (ref "C12") (pin "1") (pinfunction "1_1") (pintype "passive"))
      (node (ref "R27") (pin "2") (pinfunction "2_2") (pintype "passive"))
    )
    (net (code "41") (name "Net-(CHG_LED-PadC)") (class "Default")
      (node (ref "CHG_LED") (pin "C") (pinfunction "C_C") (pintype "passive"))
      (node (ref "R13") (pin "1") (pinfunction "1_1") (pintype "passive"))
    )
    (net (code "42") (name "Net-(DOWN-PadP$ACTIVE)") (class "Default")
      (node (ref "DOWN") (pin "P$ACTIVE") (pinfunction "P$ACTIVE_P$ACTIVE") (pintype "bidirectional"))
      (node (ref "R6") (pin "2") (pinfunction "2_2") (pintype "passive"))
    )
    (net (code "43") (name "Net-(ESP32-TXD0)") (class "Default")
      (node (ref "ESP32") (pin "35") (pinfunction "TXD0_35") (pintype "bidirectional"))
      (node (ref "R25") (pin "2") (pinfunction "2_2") (pintype "passive"))
    )
    (net (code "44") (name "Net-(LCD-LED_K-PadP$11)") (class "Default")
      (node (ref "LCD") (pin "P$11") (pinfunction "LED_K_P$11") (pintype "bidirectional"))
      (node (ref "LCD") (pin "P$12") (pinfunction "LED_K_P$12") (pintype "bidirectional"))
      (node (ref "LCD") (pin "P$13") (pinfunction "LED_K_P$13") (pintype "bidirectional"))
      (node (ref "LCD") (pin "P$14") (pinfunction "LED_K_P$14") (pintype "bidirectional"))
      (node (ref "R23") (pin "1") (pinfunction "1_1") (pintype "passive"))
    )
    (net (code "45") (name "Net-(LED-PadA)") (class "Default")
      (node (ref "LED") (pin "A") (pinfunction "A_A") (pintype "passive"))
      (node (ref "R19") (pin "2") (pinfunction "2_2") (pintype "passive"))
    )
    (net (code "46") (name "Net-(PWR-O)") (class "Default")
      (node (ref "PWR") (pin "1") (pinfunction "O_1") (pintype "passive"))
      (node (ref "VREG") (pin "3") (pinfunction "EN_3") (pintype "bidirectional"))
    )
    (net (code "47") (name "Net-(Q1-C)") (class "Default")
      (node (ref "Q1") (pin "3") (pinfunction "C_3") (pintype "passive"))
      (node (ref "R23") (pin "2") (pinfunction "2_2") (pintype "passive"))
    )
    (net (code "48") (name "Net-(Q5-B)") (class "Default")
      (node (ref "Q5") (pin "1") (pinfunction "B_1") (pintype "passive"))
      (node (ref "R17") (pin "2") (pinfunction "2_2") (pintype "passive"))
    )
    (net (code "49") (name "Net-(Q6-B)") (class "Default")
      (node (ref "Q6") (pin "1") (pinfunction "B_1") (pintype "passive"))
      (node (ref "R18") (pin "2") (pinfunction "2_2") (pintype "passive"))
    )
    (net (code "50") (name "Net-(R8-Pad1)") (class "Default")
      (node (ref "R8") (pin "1") (pinfunction "1_1") (pintype "passive"))
      (node (ref "RIGHT") (pin "P$ACTIVE") (pinfunction "P$ACTIVE_P$ACTIVE") (pintype "bidirectional"))
    )
    (net (code "51") (name "Net-(SPEAKER-+)") (class "Default")
      (node (ref "JACK") (pin "6") (pinfunction "6_6") (pintype "bidirectional"))
      (node (ref "SPEAKER") (pin "2") (pinfunction "+_2") (pintype "passive"))
    )
    (net (code "52") (name "Net-(U$1-PROG)") (class "Default")
      (node (ref "R14") (pin "1") (pinfunction "1_1") (pintype "passive"))
      (node (ref "U$1") (pin "5") (pinfunction "PROG_5") (pintype "input"))
    )
    (net (code "53") (name "Net-(U$1-STAT)") (class "Default")
      (node (ref "R13") (pin "2") (pinfunction "2_2") (pintype "passive"))
      (node (ref "U$1") (pin "1") (pinfunction "STAT_1") (pintype "output"))
    )
    (net (code "54") (name "Net-(U$23-RX)") (class "Default")
      (node (ref "R16") (pin "1") (pinfunction "1_1") (pintype "passive"))
      (node (ref "U$23") (pin "3") (pinfunction "RX_3") (pintype "bidirectional"))
    )
    (net (code "55") (name "Net-(U$23-TX)") (class "Default")
      (node (ref "R15") (pin "1") (pinfunction "1_1") (pintype "passive"))
      (node (ref "U$23") (pin "2") (pinfunction "TX_2") (pintype "bidirectional"))
    )
    (net (code "56") (name "Net-(U$23-V3)") (class "Default")
      (node (ref "C14") (pin "1") (pinfunction "1_1") (pintype "passive"))
      (node (ref "U$23") (pin "4") (pinfunction "V3_4") (pintype "bidirectional"))
    )
    (net (code "57") (name "Net-(U$23-XI)") (class "Default")
      (node (ref "U$23") (pin "7") (pinfunction "XI_7") (pintype "bidirectional"))
      (node (ref "Y1") (pin "1") (pinfunction "1_1") (pintype "passive"))
    )
    (net (code "58") (name "Net-(U$23-XO)") (class "Default")
      (node (ref "U$23") (pin "8") (pinfunction "XO_8") (pintype "bidirectional"))
      (node (ref "Y1") (pin "3") (pinfunction "3_3") (pintype "passive"))
    )
    (net (code "59") (name "Net-(U2-GAIN)") (class "Default")
      (node (ref "R2") (pin "1") (pinfunction "1_1") (pintype "passive"))
      (node (ref "U2") (pin "2") (pinfunction "GAIN_2") (pintype "bidirectional"))
    )
    (net (code "60") (name "VBAT") (class "Default")
      (node (ref "BATTERY") (pin "2") (pinfunction "+_2") (pintype "passive"))
      (node (ref "C10") (pin "1") (pinfunction "1_1") (pintype "passive"))
      (node (ref "D2") (pin "A") (pinfunction "A_A") (pintype "passive"))
      (node (ref "R10") (pin "2") (pinfunction "2_2") (pintype "passive"))
      (node (ref "U$1") (pin "3") (pinfunction "VBAT_3") (pintype "power_in"))
    )
    (net (code "61") (name "VBUS") (class "Default")
      (node (ref "C1") (pin "1") (pinfunction "1_1") (pintype "passive"))
      (node (ref "C20") (pin "1") (pinfunction "1_1") (pintype "passive"))
      (node (ref "C21") (pin "1") (pinfunction "1_1") (pintype "passive"))
      (node (ref "C4") (pin "1") (pinfunction "1_1") (pintype "passive"))
      (node (ref "CHG_LED") (pin "A") (pinfunction "A_A") (pintype "passive"))
      (node (ref "D2") (pin "C") (pinfunction "C_C") (pintype "passive"))
      (node (ref "PWR") (pin "2") (pinfunction "P_2") (pintype "passive"))
      (node (ref "U$1") (pin "4") (pinfunction "VIN_4") (pintype "power_in"))
      (node (ref "U$23") (pin "16") (pinfunction "VCC_16") (pintype "bidirectional"))
      (node (ref "USB") (pin "VBUS") (pinfunction "VBUS_VBUS") (pintype "bidirectional"))
      (node (ref "VREG") (pin "1") (pinfunction "IN_1") (pintype "bidirectional"))
    )
    (net (code "62") (name "unconnected-(ESP32-CLK-Pad20)") (class "Default")
      (node (ref "ESP32") (pin "20") (pinfunction "CLK_20") (pintype "bidirectional"))
    )
    (net (code "63") (name "unconnected-(ESP32-CMD-Pad19)") (class "Default")
      (node (ref "ESP32") (pin "19") (pinfunction "CMD_19") (pintype "bidirectional"))
    )
    (net (code "64") (name "unconnected-(ESP32-NC-Pad27)") (class "Default")
      (node (ref "ESP32") (pin "27") (pinfunction "NC_27") (pintype "bidirectional"))
    )
    (net (code "65") (name "unconnected-(ESP32-NC-Pad28)") (class "Default")
      (node (ref "ESP32") (pin "28") (pinfunction "NC_28") (pintype "bidirectional"))
    )
    (net (code "66") (name "unconnected-(ESP32-NC-Pad32)") (class "Default")
      (node (ref "ESP32") (pin "32") (pinfunction "NC_32") (pintype "bidirectional"))
    )
    (net (code "67") (name "unconnected-(ESP32-SD0-Pad21)") (class "Default")
      (node (ref "ESP32") (pin "21") (pinfunction "SD0_21") (pintype "bidirectional"))
    )
    (net (code "68") (name "unconnected-(ESP32-SD1-Pad22)") (class "Default")
      (node (ref "ESP32") (pin "22") (pinfunction "SD1_22") (pintype "bidirectional"))
    )
    (net (code "69") (name "unconnected-(ESP32-SD2-Pad17)") (class "Default")
      (node (ref "ESP32") (pin "17") (pinfunction "SD2_17") (pintype "bidirectional"))
    )
    (net (code "70") (name "unconnected-(ESP32-SD3-Pad18)") (class "Default")
      (node (ref "ESP32") (pin "18") (pinfunction "SD3_18") (pintype "bidirectional"))
    )
    (net (code "71") (name "unconnected-(JACK-Pad2)") (class "Default")
      (node (ref "JACK") (pin "2") (pinfunction "2_2") (pintype "bidirectional"))
    )
    (net (code "72") (name "unconnected-(JACK-Pad4)") (class "Default")
      (node (ref "JACK") (pin "4") (pinfunction "4_4") (pintype "bidirectional"))
    )
    (net (code "73") (name "unconnected-(LCD-XL-PadP$15)") (class "Default")
      (node (ref "LCD") (pin "P$15") (pinfunction "XL_P$15") (pintype "bidirectional"))
    )
    (net (code "74") (name "unconnected-(LCD-XR-PadP$16)") (class "Default")
      (node (ref "LCD") (pin "P$16") (pinfunction "XR_P$16") (pintype "bidirectional"))
    )
    (net (code "75") (name "unconnected-(LCD-YD-PadP$17)") (class "Default")
      (node (ref "LCD") (pin "P$17") (pinfunction "YD_P$17") (pintype "bidirectional"))
    )
    (net (code "76") (name "unconnected-(LCD-YU-PadP$18)") (class "Default")
      (node (ref "LCD") (pin "P$18") (pinfunction "YU_P$18") (pintype "bidirectional"))
    )
    (net (code "77") (name "unconnected-(PWR-S-Pad3)") (class "Default")
      (node (ref "PWR") (pin "3") (pinfunction "S_3") (pintype "passive"))
    )
    (net (code "78") (name "unconnected-(SD_CARD-PadCD)") (class "Default")
      (node (ref "SD_CARD") (pin "CD") (pinfunction "CD_CD") (pintype "bidirectional"))
    )
    (net (code "79") (name "unconnected-(SD_CARD-PadDAT1)") (class "Default")
      (node (ref "SD_CARD") (pin "DAT1") (pinfunction "DAT1_DAT1") (pintype "bidirectional"))
    )
    (net (code "80") (name "unconnected-(SD_CARD-PadDAT2)") (class "Default")
      (node (ref "SD_CARD") (pin "DAT2") (pinfunction "DAT2_DAT2") (pintype "bidirectional"))
    )
    (net (code "81") (name "unconnected-(U$23-CTS-Pad9)") (class "Default")
      (node (ref "U$23") (pin "9") (pinfunction "CTS_9") (pintype "bidirectional"))
    )
    (net (code "82") (name "unconnected-(U$23-DCD-Pad12)") (class "Default")
      (node (ref "U$23") (pin "12") (pinfunction "DCD_12") (pintype "bidirectional"))
    )
    (net (code "83") (name "unconnected-(U$23-DSR-Pad10)") (class "Default")
      (node (ref "U$23") (pin "10") (pinfunction "DSR_10") (pintype "bidirectional"))
    )
    (net (code "84") (name "unconnected-(U$23-RI-Pad11)") (class "Default")
      (node (ref "U$23") (pin "11") (pinfunction "RI_11") (pintype "bidirectional"))
    )
    (net (code "85") (name "unconnected-(U$23-RS232-Pad15)") (class "Default")
      (node (ref "U$23") (pin "15") (pinfunction "RS232_15") (pintype "bidirectional"))
    )
    (net (code "86") (name "unconnected-(VREG-P4-Pad4)") (class "Default")
      (node (ref "VREG") (pin "4") (pinfunction "P4_4") (pintype "bidirectional"))
    )
  )
)
